# Sheet_2.net
KiCad netlist of a schematic drawn in EasyEDA
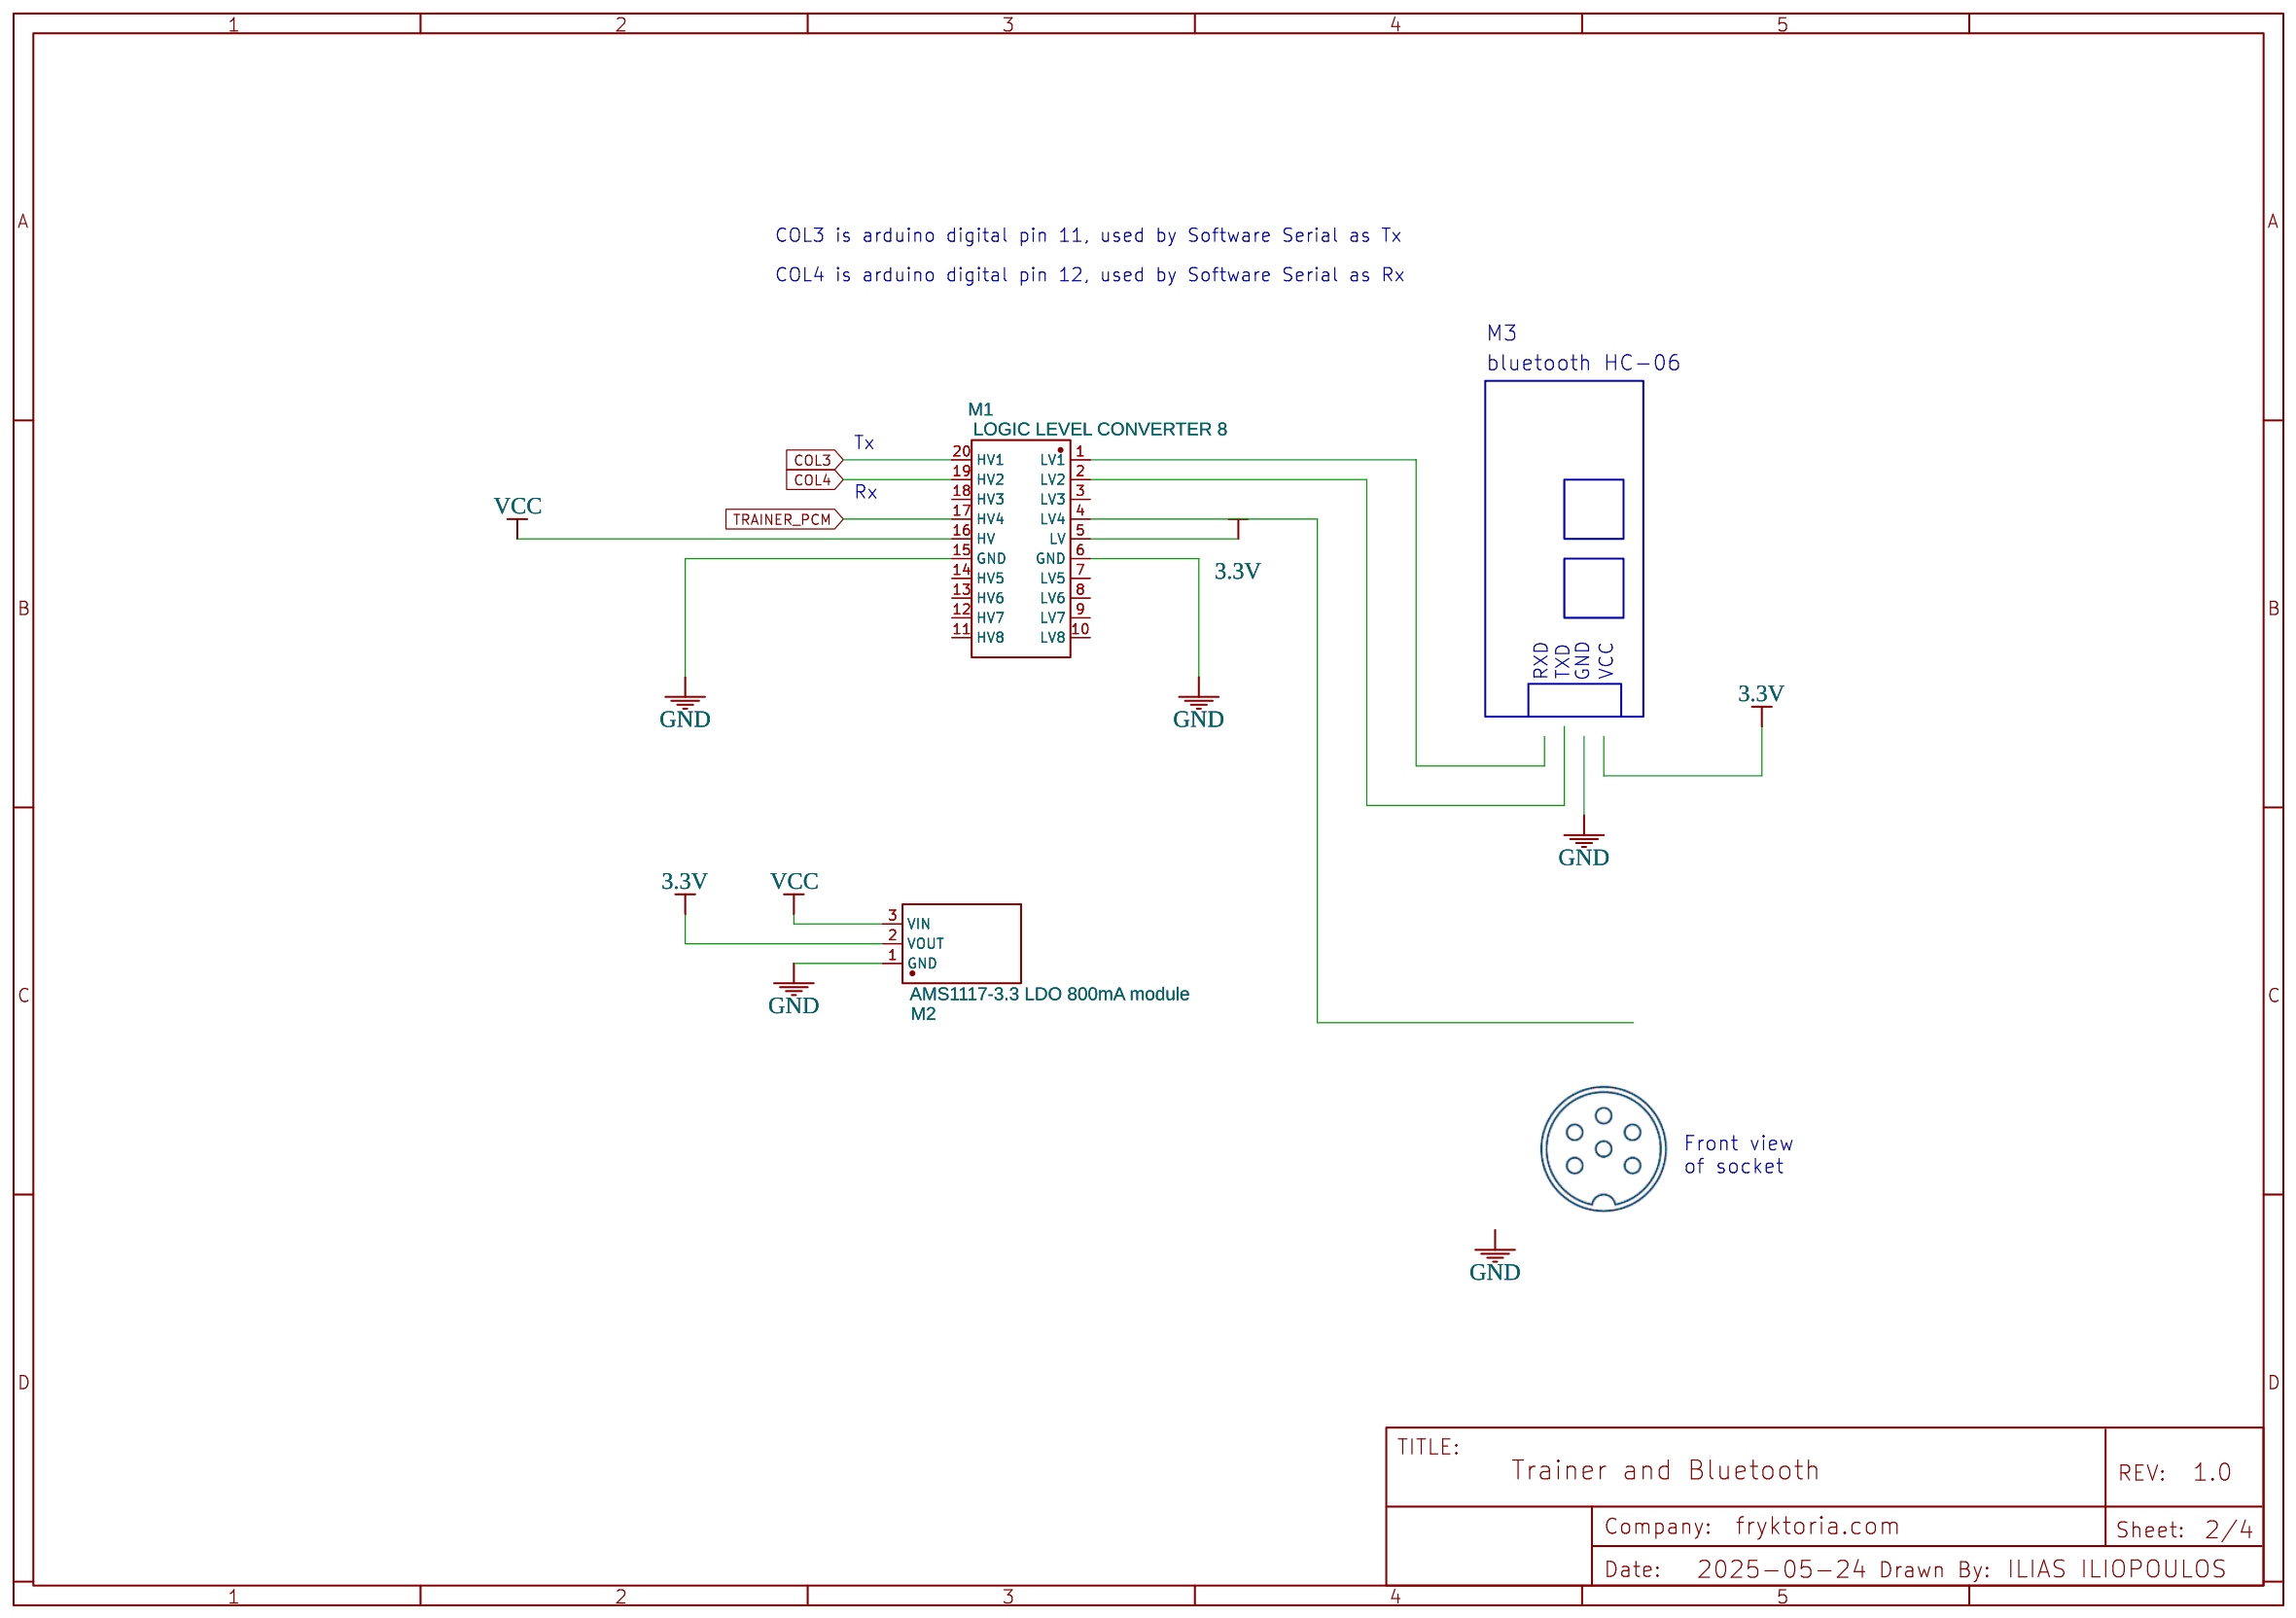
[diagram p0: schematic sheet]

(export (version "E")
  (design (tool "Eeschema 10.0.6"))
  (components
    (comp (ref "M1")
      (value "LOGIC LEVEL CONVERTER 8")
      (fields (field (name "Manufacturer Part") "Level Converter 8"))
      (libsource (lib "") (part "LEVEL CONVERTER 8"))
    )
    (comp (ref "M2")
      (value "AMS1117-3.3 LDO 800mA module")
      (fields (field (name "Manufacturer Part") "AMS1117-3.3") (field (name "Manufacturer") "GOODWORK(固得沃克)"))
      (libsource (lib "") (part "AMS1117-3.3_C6067465"))
    )
  )
  (nets
    (net (code "1") (name "3.3V") (class "Default")
      (node (ref "M1") (pin "5") (pinfunction "LV_5") (pintype "unspecified"))
      (node (ref "M2") (pin "2") (pinfunction "VOUT_2") (pintype "unspecified"))
    )
    (net (code "2") (name "COL3") (class "Default")
      (node (ref "M1") (pin "20") (pinfunction "HV1_20") (pintype "unspecified"))
    )
    (net (code "3") (name "COL4") (class "Default")
      (node (ref "M1") (pin "19") (pinfunction "HV2_19") (pintype "unspecified"))
    )
    (net (code "4") (name "GND") (class "Default")
      (node (ref "M1") (pin "15") (pinfunction "GND_15") (pintype "unspecified"))
      (node (ref "M1") (pin "6") (pinfunction "GND_6") (pintype "unspecified"))
      (node (ref "M2") (pin "1") (pinfunction "GND_1") (pintype "unspecified"))
    )
    (net (code "5") (name "TRAINER_PCM") (class "Default")
      (node (ref "M1") (pin "17") (pinfunction "HV4_17") (pintype "unspecified"))
    )
    (net (code "6") (name "VCC") (class "Default")
      (node (ref "M1") (pin "16") (pinfunction "HV_16") (pintype "unspecified"))
      (node (ref "M2") (pin "3") (pinfunction "VIN_3") (pintype "unspecified"))
    )
    (net (code "7") (name "unconnected-(M1-HV3-Pad18)") (class "Default")
      (node (ref "M1") (pin "18") (pinfunction "HV3_18") (pintype "unspecified"))
    )
    (net (code "8") (name "unconnected-(M1-HV5-Pad14)") (class "Default")
      (node (ref "M1") (pin "14") (pinfunction "HV5_14") (pintype "unspecified"))
    )
    (net (code "9") (name "unconnected-(M1-HV6-Pad13)") (class "Default")
      (node (ref "M1") (pin "13") (pinfunction "HV6_13") (pintype "unspecified"))
    )
    (net (code "10") (name "unconnected-(M1-HV7-Pad12)") (class "Default")
      (node (ref "M1") (pin "12") (pinfunction "HV7_12") (pintype "unspecified"))
    )
    (net (code "11") (name "unconnected-(M1-HV8-Pad11)") (class "Default")
      (node (ref "M1") (pin "11") (pinfunction "HV8_11") (pintype "unspecified"))
    )
    (net (code "12") (name "unconnected-(M1-LV1-Pad1)") (class "Default")
      (node (ref "M1") (pin "1") (pinfunction "LV1_1") (pintype "unspecified"))
    )
    (net (code "13") (name "unconnected-(M1-LV2-Pad2)") (class "Default")
      (node (ref "M1") (pin "2") (pinfunction "LV2_2") (pintype "unspecified"))
    )
    (net (code "14") (name "unconnected-(M1-LV3-Pad3)") (class "Default")
      (node (ref "M1") (pin "3") (pinfunction "LV3_3") (pintype "unspecified"))
    )
    (net (code "15") (name "unconnected-(M1-LV4-Pad4)") (class "Default")
      (node (ref "M1") (pin "4") (pinfunction "LV4_4") (pintype "unspecified"))
    )
    (net (code "16") (name "unconnected-(M1-LV5-Pad7)") (class "Default")
      (node (ref "M1") (pin "7") (pinfunction "LV5_7") (pintype "unspecified"))
    )
    (net (code "17") (name "unconnected-(M1-LV6-Pad8)") (class "Default")
      (node (ref "M1") (pin "8") (pinfunction "LV6_8") (pintype "unspecified"))
    )
    (net (code "18") (name "unconnected-(M1-LV7-Pad9)") (class "Default")
      (node (ref "M1") (pin "9") (pinfunction "LV7_9") (pintype "unspecified"))
    )
    (net (code "19") (name "unconnected-(M1-LV8-Pad10)") (class "Default")
      (node (ref "M1") (pin "10") (pinfunction "LV8_10") (pintype "unspecified"))
    )
  )
)
